# VSR_Mini_Mega_rev_1_300_new_XH_connector.net
KiCad netlist of a schematic drawn in EAGLE
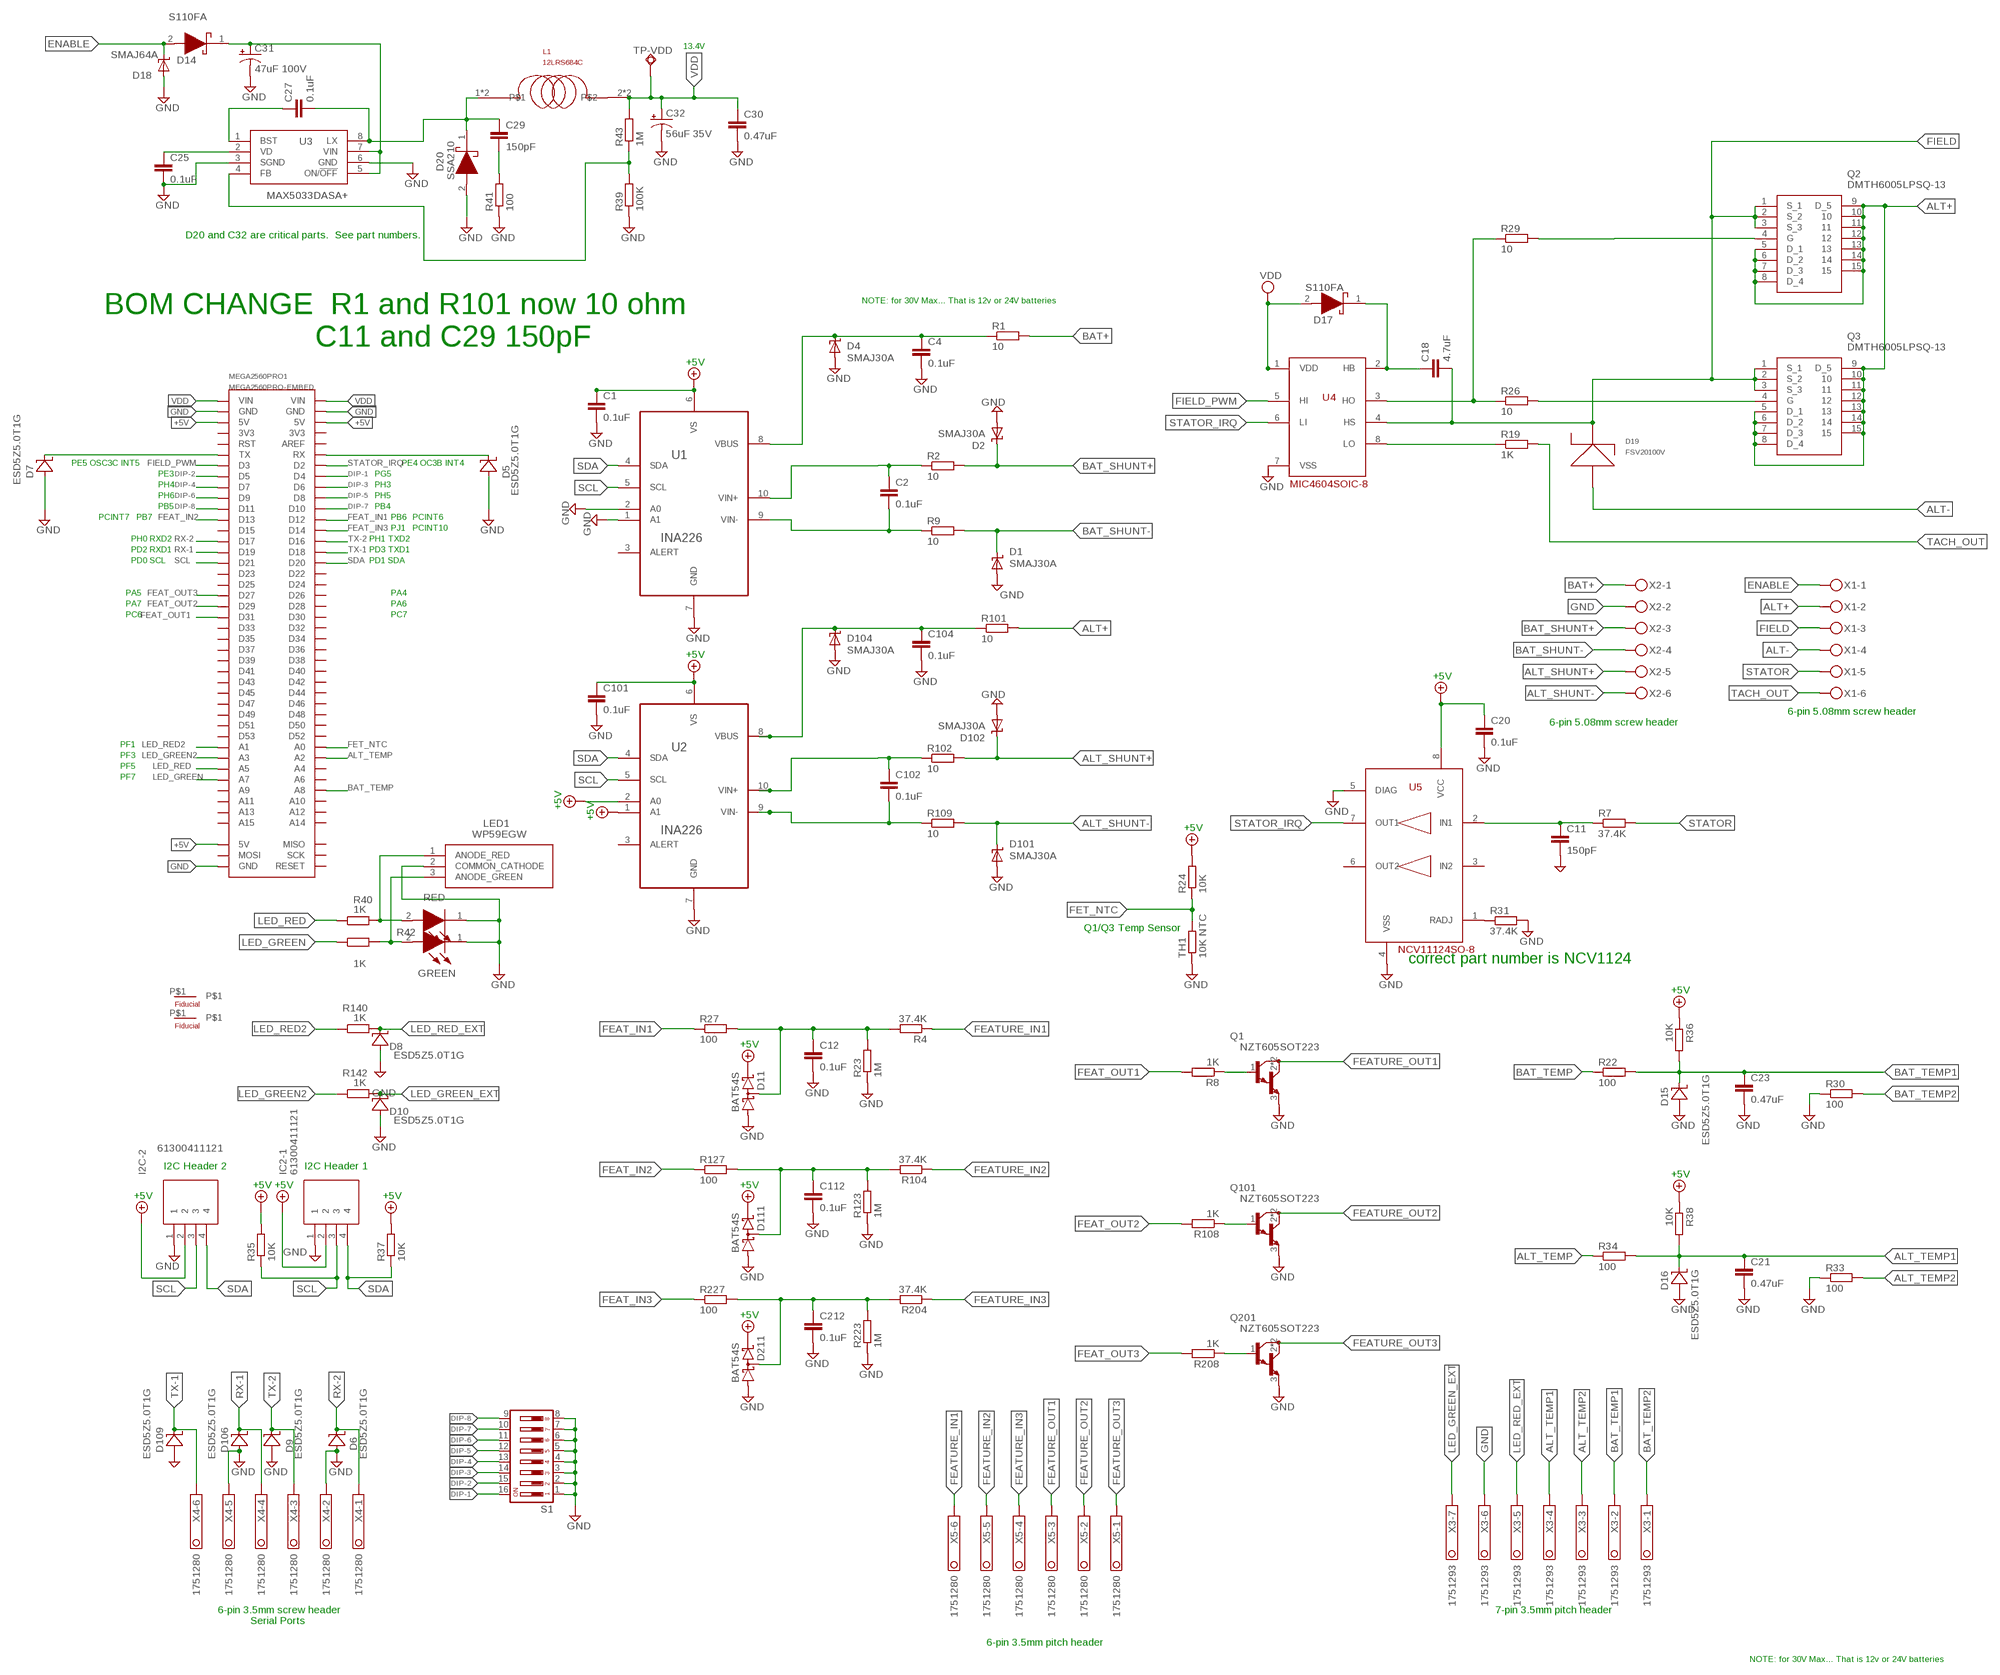
[diagram p0: schematic, sheet 1]

(export (version "E")
  (design (tool "Eeschema 10.0.6"))
  (components
    (comp (ref "C1")
      (value "0.1uF")
      (footprint "eagle-import:C0603")
      (libsource (lib "eagle-import") (part "C-EUC0603"))
    )
    (comp (ref "C2")
      (value "0.1uF")
      (footprint "eagle-import:C0603")
      (libsource (lib "eagle-import") (part "C-EUC0603"))
    )
    (comp (ref "C4")
      (value "0.1uF")
      (footprint "eagle-import:C0603")
      (libsource (lib "eagle-import") (part "C-EUC0603"))
    )
    (comp (ref "C11")
      (value "150pF")
      (footprint "eagle-import:C0603")
      (libsource (lib "eagle-import") (part "C-EUC0603"))
    )
    (comp (ref "C12")
      (value "0.1uF")
      (footprint "eagle-import:C0603")
      (libsource (lib "eagle-import") (part "C-EUC0603"))
    )
    (comp (ref "C18")
      (value "4.7uF")
      (footprint "eagle-import:C0603K")
      (libsource (lib "eagle-import") (part "C-EUC0603K"))
    )
    (comp (ref "C20")
      (value "0.1uF")
      (footprint "eagle-import:C0603")
      (libsource (lib "eagle-import") (part "C-EUC0603"))
    )
    (comp (ref "C21")
      (value "0.47uF")
      (footprint "eagle-import:C0603")
      (libsource (lib "eagle-import") (part "C-EUC0603"))
    )
    (comp (ref "C23")
      (value "0.47uF")
      (footprint "eagle-import:C0603")
      (libsource (lib "eagle-import") (part "C-EUC0603"))
    )
    (comp (ref "C25")
      (value "0.1uF")
      (footprint "eagle-import:C0603")
      (libsource (lib "eagle-import") (part "C-EUC0603"))
    )
    (comp (ref "C27")
      (value "0.1uF")
      (footprint "eagle-import:C0603")
      (libsource (lib "eagle-import") (part "C-EUC0603"))
    )
    (comp (ref "C29")
      (value "150pF")
      (footprint "eagle-import:C0603")
      (libsource (lib "eagle-import") (part "C-EUC0603"))
    )
    (comp (ref "C30")
      (value "0.47uF")
      (footprint "eagle-import:C0603")
      (libsource (lib "eagle-import") (part "C-EUC0603"))
    )
    (comp (ref "C31")
      (value "47uF 100V")
      (footprint "eagle-import:CAPPRD500W60D1000H1250B")
      (libsource (lib "eagle-import") (part "CPOL-USCAPPRD500W60D100H1250B"))
    )
    (comp (ref "C32")
      (value "56uF 35V")
      (footprint "eagle-import:CAPPRD250W50D630H1100B")
      (libsource (lib "eagle-import") (part "CPOL-US"))
    )
    (comp (ref "C101")
      (value "0.1uF")
      (footprint "eagle-import:C0603")
      (libsource (lib "eagle-import") (part "C-EUC0603"))
    )
    (comp (ref "C102")
      (value "0.1uF")
      (footprint "eagle-import:C0603")
      (libsource (lib "eagle-import") (part "C-EUC0603"))
    )
    (comp (ref "C104")
      (value "0.1uF")
      (footprint "eagle-import:C0603")
      (libsource (lib "eagle-import") (part "C-EUC0603"))
    )
    (comp (ref "C112")
      (value "0.1uF")
      (footprint "eagle-import:C0603")
      (libsource (lib "eagle-import") (part "C-EUC0603"))
    )
    (comp (ref "C212")
      (value "0.1uF")
      (footprint "eagle-import:C0603")
      (libsource (lib "eagle-import") (part "C-EUC0603"))
    )
    (comp (ref "D1")
      (value "SMAJ30A")
      (footprint "eagle-import:SMBJ")
      (libsource (lib "eagle-import") (part "SUPPRESSOR-SMBJ"))
    )
    (comp (ref "D2")
      (value "SMAJ30A")
      (footprint "eagle-import:SMBJ")
      (libsource (lib "eagle-import") (part "SUPPRESSOR-SMBJ"))
    )
    (comp (ref "D4")
      (value "SMAJ30A")
      (footprint "eagle-import:SMBJ")
      (libsource (lib "eagle-import") (part "SUPPRESSOR-SMBJ"))
    )
    (comp (ref "D5")
      (value "ESD5Z5.0T1G")
      (footprint "eagle-import:SOD523")
      (libsource (lib "eagle-import") (part "ESD5Z5.0T1G"))
    )
    (comp (ref "D6")
      (value "ESD5Z5.0T1G")
      (footprint "eagle-import:SOD523")
      (libsource (lib "eagle-import") (part "ESD5Z5.0T1G"))
    )
    (comp (ref "D7")
      (value "ESD5Z5.0T1G")
      (footprint "eagle-import:SOD523")
      (libsource (lib "eagle-import") (part "ESD5Z5.0T1G"))
    )
    (comp (ref "D8")
      (value "ESD5Z5.0T1G")
      (footprint "eagle-import:SOD523")
      (libsource (lib "eagle-import") (part "ESD5Z5.0T1G"))
    )
    (comp (ref "D9")
      (value "ESD5Z5.0T1G")
      (footprint "eagle-import:SOD523")
      (libsource (lib "eagle-import") (part "ESD5Z5.0T1G"))
    )
    (comp (ref "D10")
      (value "ESD5Z5.0T1G")
      (footprint "eagle-import:SOD523")
      (libsource (lib "eagle-import") (part "ESD5Z5.0T1G"))
    )
    (comp (ref "D11")
      (value "BAT54S")
      (footprint "eagle-import:SOT23")
      (libsource (lib "eagle-import") (part "BAT54S"))
    )
    (comp (ref "D14")
      (value "S110FA")
      (footprint "eagle-import:SODFL3618X143N")
      (fields (field (name "MOUSER_PART_NUMBER") "512-S110FA"))
      (libsource (lib "eagle-import") (part "S110FA"))
    )
    (comp (ref "D15")
      (value "ESD5Z5.0T1G")
      (footprint "eagle-import:SOD523")
      (libsource (lib "eagle-import") (part "ESD5Z5.0T1G"))
    )
    (comp (ref "D16")
      (value "ESD5Z5.0T1G")
      (footprint "eagle-import:SOD523")
      (libsource (lib "eagle-import") (part "ESD5Z5.0T1G"))
    )
    (comp (ref "D17")
      (value "S110FA")
      (footprint "eagle-import:SODFL3618X143N")
      (fields (field (name "MOUSER_PART_NUMBER") "512-S110FA"))
      (libsource (lib "eagle-import") (part "S110FA"))
    )
    (comp (ref "D18")
      (value "SMAJ64A")
      (footprint "eagle-import:SMBJ")
      (libsource (lib "eagle-import") (part "SUPPRESSOR-SMBJ"))
    )
    (comp (ref "D19")
      (value "FSV20100V")
      (footprint "eagle-import:TO-277")
      (fields (field (name "MF") "ON Semiconductor"))
      (libsource (lib "eagle-import") (part "FSV20100V"))
    )
    (comp (ref "D20")
      (value "SSA210")
      (footprint "eagle-import:DIOM5227X270N")
      (fields (field (name "MOUSER_PART_NUMBER") "512-SSA210"))
      (libsource (lib "eagle-import") (part "SSA210"))
    )
    (comp (ref "D101")
      (value "SMAJ30A")
      (footprint "eagle-import:SMBJ")
      (libsource (lib "eagle-import") (part "SUPPRESSOR-SMBJ"))
    )
    (comp (ref "D102")
      (value "SMAJ30A")
      (footprint "eagle-import:SMBJ")
      (libsource (lib "eagle-import") (part "SUPPRESSOR-SMBJ"))
    )
    (comp (ref "D104")
      (value "SMAJ30A")
      (footprint "eagle-import:SMBJ")
      (libsource (lib "eagle-import") (part "SUPPRESSOR-SMBJ"))
    )
    (comp (ref "D106")
      (value "ESD5Z5.0T1G")
      (footprint "eagle-import:SOD523")
      (libsource (lib "eagle-import") (part "ESD5Z5.0T1G"))
    )
    (comp (ref "D109")
      (value "ESD5Z5.0T1G")
      (footprint "eagle-import:SOD523")
      (libsource (lib "eagle-import") (part "ESD5Z5.0T1G"))
    )
    (comp (ref "D111")
      (value "BAT54S")
      (footprint "eagle-import:SOT23")
      (libsource (lib "eagle-import") (part "BAT54S"))
    )
    (comp (ref "D211")
      (value "BAT54S")
      (footprint "eagle-import:SOT23")
      (libsource (lib "eagle-import") (part "BAT54S"))
    )
    (comp (ref "FIDUCIAL1")
      (value "FIDUCIAL060")
      (footprint "eagle-import:FIDUCIAL060")
      (libsource (lib "eagle-import") (part "FIDUCIAL060"))
    )
    (comp (ref "FIDUCIAL2")
      (value "FIDUCIAL060")
      (footprint "eagle-import:FIDUCIAL060")
      (libsource (lib "eagle-import") (part "FIDUCIAL060"))
    )
    (comp (ref "GREEN")
      (value "599-0110-007F")
      (footprint "eagle-import:LEDM2012X90N")
      (fields (field (name "MOUSER_PART_NUMBER") "645-599-0110-007F"))
      (libsource (lib "eagle-import") (part "599-0110-007F"))
    )
    (comp (ref "I2C-2")
      (value "61300411121")
      (footprint "eagle-import:HDRV4W95P0X254_1X4_1016X254X85")
      (fields (field (name "MOUSER_PART_NUMBER") "710-61300411121"))
      (libsource (lib "eagle-import") (part "61300411121"))
    )
    (comp (ref "IC2-1")
      (value "61300411121")
      (footprint "eagle-import:HDRV4W95P0X254_1X4_1016X254X85")
      (fields (field (name "MOUSER_PART_NUMBER") "710-61300411121"))
      (libsource (lib "eagle-import") (part "61300411121"))
    )
    (comp (ref "L1")
      (value "12LRS684C")
      (footprint "eagle-import:IND_12LRS156C")
      (libsource (lib "eagle-import") (part "12LRS684C"))
    )
    (comp (ref "LED1")
      (value "WP59EGW")
      (footprint "eagle-import:T-1_3_4(5MM)_BI-COLOR_INDICATO")
      (fields (field (name "MOUSER_PART_NUMBER") "604-WP59EGW"))
      (libsource (lib "eagle-import") (part "WP59EGW"))
    )
    (comp (ref "MEGA2560PRO1")
      (value "MEGA2560PRO-EMBED")
      (footprint "eagle-import:MEGA2560PRO-EMBED")
      (libsource (lib "eagle-import") (part "MEGA2560PRO-EMBED"))
    )
    (comp (ref "Q1")
      (value "NZT605SOT223")
      (footprint "eagle-import:SOT223")
      (libsource (lib "eagle-import") (part "NZT605SOT223"))
    )
    (comp (ref "Q2")
      (value "DMTH6005LPSQ-13")
      (footprint "eagle-import:DMTH6005LPSQ13")
      (fields (field (name "MOUSER_PART_NUMBER") "621-DMTH6005LPSQ-13"))
      (libsource (lib "eagle-import") (part "DMTH6005LPSQ-13"))
    )
    (comp (ref "Q3")
      (value "DMTH6005LPSQ-13")
      (footprint "eagle-import:DMTH6005LPSQ13")
      (fields (field (name "MOUSER_PART_NUMBER") "621-DMTH6005LPSQ-13"))
      (libsource (lib "eagle-import") (part "DMTH6005LPSQ-13"))
    )
    (comp (ref "Q101")
      (value "NZT605SOT223")
      (footprint "eagle-import:SOT223")
      (libsource (lib "eagle-import") (part "NZT605SOT223"))
    )
    (comp (ref "Q201")
      (value "NZT605SOT223")
      (footprint "eagle-import:SOT223")
      (libsource (lib "eagle-import") (part "NZT605SOT223"))
    )
    (comp (ref "R1")
      (value "10")
      (footprint "eagle-import:R0603")
      (libsource (lib "eagle-import") (part "R-EU_R0603"))
    )
    (comp (ref "R2")
      (value "10")
      (footprint "eagle-import:R0603")
      (libsource (lib "eagle-import") (part "R-EU_R0603"))
    )
    (comp (ref "R4")
      (value "37.4K")
      (footprint "eagle-import:R0603")
      (libsource (lib "eagle-import") (part "R-EU_R0603"))
    )
    (comp (ref "R7")
      (value "37.4K")
      (footprint "eagle-import:R0603")
      (libsource (lib "eagle-import") (part "R-EU_R0603"))
    )
    (comp (ref "R8")
      (value "1K")
      (footprint "eagle-import:R0603")
      (libsource (lib "eagle-import") (part "R-EU_R0603"))
    )
    (comp (ref "R9")
      (value "10")
      (footprint "eagle-import:R0603")
      (libsource (lib "eagle-import") (part "R-EU_R0603"))
    )
    (comp (ref "R19")
      (value "1K")
      (footprint "eagle-import:R0603")
      (libsource (lib "eagle-import") (part "R-EU_R0603"))
    )
    (comp (ref "R22")
      (value "100")
      (footprint "eagle-import:R0603")
      (libsource (lib "eagle-import") (part "R-EU_R0603"))
    )
    (comp (ref "R23")
      (value "1M")
      (footprint "eagle-import:R0603")
      (libsource (lib "eagle-import") (part "R-EU_R0603"))
    )
    (comp (ref "R24")
      (value "10K")
      (footprint "eagle-import:R0603")
      (libsource (lib "eagle-import") (part "R-EU_R0603"))
    )
    (comp (ref "R26")
      (value "10")
      (footprint "eagle-import:R0603")
      (libsource (lib "eagle-import") (part "R-EU_R0603"))
    )
    (comp (ref "R27")
      (value "100")
      (footprint "eagle-import:R0603")
      (libsource (lib "eagle-import") (part "R-EU_R0603"))
    )
    (comp (ref "R29")
      (value "10")
      (footprint "eagle-import:R0603")
      (libsource (lib "eagle-import") (part "R-EU_R0603"))
    )
    (comp (ref "R30")
      (value "100")
      (footprint "eagle-import:R0603")
      (libsource (lib "eagle-import") (part "R-EU_R0603"))
    )
    (comp (ref "R31")
      (value "37.4K")
      (footprint "eagle-import:R0603")
      (libsource (lib "eagle-import") (part "R-EU_R0603"))
    )
    (comp (ref "R33")
      (value "100")
      (footprint "eagle-import:R0603")
      (libsource (lib "eagle-import") (part "R-EU_R0603"))
    )
    (comp (ref "R34")
      (value "100")
      (footprint "eagle-import:R0603")
      (libsource (lib "eagle-import") (part "R-EU_R0603"))
    )
    (comp (ref "R35")
      (value "10K")
      (footprint "eagle-import:R0603")
      (libsource (lib "eagle-import") (part "R-EU_R0603"))
    )
    (comp (ref "R36")
      (value "10K")
      (footprint "eagle-import:R0603")
      (libsource (lib "eagle-import") (part "R-EU_R0603"))
    )
    (comp (ref "R37")
      (value "10K")
      (footprint "eagle-import:R0603")
      (libsource (lib "eagle-import") (part "R-EU_R0603"))
    )
    (comp (ref "R38")
      (value "10K")
      (footprint "eagle-import:R0603")
      (libsource (lib "eagle-import") (part "R-EU_R0603"))
    )
    (comp (ref "R39")
      (value "100K")
      (footprint "eagle-import:R0603")
      (libsource (lib "eagle-import") (part "R-EU_R0603"))
    )
    (comp (ref "R40")
      (value "1K")
      (footprint "eagle-import:R0603")
      (libsource (lib "eagle-import") (part "R-EU_R0603"))
    )
    (comp (ref "R41")
      (value "100")
      (footprint "eagle-import:R0603")
      (libsource (lib "eagle-import") (part "R-EU_R0603"))
    )
    (comp (ref "R42")
      (value "1K")
      (footprint "eagle-import:R0603")
      (libsource (lib "eagle-import") (part "R-EU_R0603"))
    )
    (comp (ref "R43")
      (value "1M")
      (footprint "eagle-import:R0603")
      (libsource (lib "eagle-import") (part "R-EU_R0603"))
    )
    (comp (ref "R101")
      (value "10")
      (footprint "eagle-import:R0603")
      (libsource (lib "eagle-import") (part "R-EU_R0603"))
    )
    (comp (ref "R102")
      (value "10")
      (footprint "eagle-import:R0603")
      (libsource (lib "eagle-import") (part "R-EU_R0603"))
    )
    (comp (ref "R104")
      (value "37.4K")
      (footprint "eagle-import:R0603")
      (libsource (lib "eagle-import") (part "R-EU_R0603"))
    )
    (comp (ref "R108")
      (value "1K")
      (footprint "eagle-import:R0603")
      (libsource (lib "eagle-import") (part "R-EU_R0603"))
    )
    (comp (ref "R109")
      (value "10")
      (footprint "eagle-import:R0603")
      (libsource (lib "eagle-import") (part "R-EU_R0603"))
    )
    (comp (ref "R123")
      (value "1M")
      (footprint "eagle-import:R0603")
      (libsource (lib "eagle-import") (part "R-EU_R0603"))
    )
    (comp (ref "R127")
      (value "100")
      (footprint "eagle-import:R0603")
      (libsource (lib "eagle-import") (part "R-EU_R0603"))
    )
    (comp (ref "R140")
      (value "1K")
      (footprint "eagle-import:R0603")
      (libsource (lib "eagle-import") (part "R-EU_R0603"))
    )
    (comp (ref "R142")
      (value "1K")
      (footprint "eagle-import:R0603")
      (libsource (lib "eagle-import") (part "R-EU_R0603"))
    )
    (comp (ref "R204")
      (value "37.4K")
      (footprint "eagle-import:R0603")
      (libsource (lib "eagle-import") (part "R-EU_R0603"))
    )
    (comp (ref "R208")
      (value "1K")
      (footprint "eagle-import:R0603")
      (libsource (lib "eagle-import") (part "R-EU_R0603"))
    )
    (comp (ref "R223")
      (value "1M")
      (footprint "eagle-import:R0603")
      (libsource (lib "eagle-import") (part "R-EU_R0603"))
    )
    (comp (ref "R227")
      (value "100")
      (footprint "eagle-import:R0603")
      (libsource (lib "eagle-import") (part "R-EU_R0603"))
    )
    (comp (ref "RED")
      (value "599-0110-007F")
      (footprint "eagle-import:LEDM2012X90N")
      (fields (field (name "MOUSER_PART_NUMBER") "645-599-0110-007F"))
      (libsource (lib "eagle-import") (part "599-0110-007F"))
    )
    (comp (ref "S1")
      (value "DP08")
      (footprint "eagle-import:DP-08")
      (libsource (lib "eagle-import") (part "DP08"))
    )
    (comp (ref "TH1")
      (value "10K NTC")
      (footprint "eagle-import:R0402")
      (libsource (lib "eagle-import") (part "R-EU_R0402"))
    )
    (comp (ref "TP-VDD")
      (value "TPSQTP20SQ")
      (footprint "eagle-import:TP20SQ")
      (libsource (lib "eagle-import") (part "TPSQTP20SQ"))
    )
    (comp (ref "U1")
      (value "INA226")
      (footprint "eagle-import:SOP50P490X110-10N")
      (fields (field (name "MPN") "INA226AIDGSR"))
      (libsource (lib "eagle-import") (part "INA226"))
    )
    (comp (ref "U2")
      (value "INA226")
      (footprint "eagle-import:SOP50P490X110-10N")
      (fields (field (name "MPN") "INA226AIDGSR"))
      (libsource (lib "eagle-import") (part "INA226"))
    )
    (comp (ref "U3")
      (value "MAX5033DASA+")
      (footprint "eagle-import:SOIC127P600X175-8N")
      (fields (field (name "MOUSER_PART_NUMBER") "700-MAX5033DASA"))
      (libsource (lib "eagle-import") (part "MAX5033DASA+"))
    )
    (comp (ref "U4")
      (value "MIC4604SOIC-8")
      (footprint "eagle-import:SOIC8")
      (libsource (lib "eagle-import") (part "MIC4604SOIC-8"))
    )
    (comp (ref "U5")
      (value "NCV11124SO-8")
      (footprint "eagle-import:SO-8")
      (libsource (lib "eagle-import") (part "NCV11124SO-8"))
    )
    (comp (ref "X1")
      (value "MKDSN1,5/6-5,08")
      (footprint "eagle-import:MKDSN1,5_6-5,08")
      (libsource (lib "eagle-import") (part "MKDSN1,5/6-5,08"))
    )
    (comp (ref "X2")
      (value "MKDSN1,5/6-5,08")
      (footprint "eagle-import:MKDSN1,5_6-5,08")
      (libsource (lib "eagle-import") (part "MKDSN1,5/6-5,08"))
    )
    (comp (ref "X3")
      (value "1751293")
      (footprint "eagle-import:1751293")
      (libsource (lib "eagle-import") (part "1751293"))
    )
    (comp (ref "X4")
      (value "1751280")
      (footprint "eagle-import:1751280")
      (libsource (lib "eagle-import") (part "1751280"))
    )
    (comp (ref "X5")
      (value "1751280")
      (footprint "eagle-import:1751280")
      (libsource (lib "eagle-import") (part "1751280"))
    )
  )
  (nets
    (net (code "1") (name "+5V") (class "Default")
      (node (ref "C1") (pin "1") (pinfunction "1_1") (pintype "passive"))
      (node (ref "C101") (pin "1") (pinfunction "1_1") (pintype "passive"))
      (node (ref "C20") (pin "1") (pinfunction "1_1") (pintype "passive"))
      (node (ref "D11") (pin "2") (pinfunction "C2_2") (pintype "passive"))
      (node (ref "D111") (pin "2") (pinfunction "C2_2") (pintype "passive"))
      (node (ref "D211") (pin "2") (pinfunction "C2_2") (pintype "passive"))
      (node (ref "I2C-2") (pin "2") (pinfunction "2_2") (pintype "bidirectional"))
      (node (ref "IC2-1") (pin "2") (pinfunction "2_2") (pintype "bidirectional"))
      (node (ref "MEGA2560PRO1") (pin "5V@1") (pinfunction "5V_5V@1") (pintype "bidirectional"))
      (node (ref "MEGA2560PRO1") (pin "5V@2") (pinfunction "5V_5V@2") (pintype "bidirectional"))
      (node (ref "MEGA2560PRO1") (pin "5V@3") (pinfunction "5V_5V@3") (pintype "bidirectional"))
      (node (ref "R24") (pin "2") (pinfunction "2_2") (pintype "passive"))
      (node (ref "R35") (pin "2") (pinfunction "2_2") (pintype "passive"))
      (node (ref "R36") (pin "1") (pinfunction "1_1") (pintype "passive"))
      (node (ref "R37") (pin "2") (pinfunction "2_2") (pintype "passive"))
      (node (ref "R38") (pin "1") (pinfunction "1_1") (pintype "passive"))
      (node (ref "U1") (pin "6") (pinfunction "VS_6") (pintype "power_in"))
      (node (ref "U2") (pin "1") (pinfunction "A1_1") (pintype "input"))
      (node (ref "U2") (pin "2") (pinfunction "A0_2") (pintype "input"))
      (node (ref "U2") (pin "6") (pinfunction "VS_6") (pintype "power_in"))
      (node (ref "U5") (pin "8") (pinfunction "VCC_8") (pintype "bidirectional"))
    )
    (net (code "2") (name "ALT+") (class "Default")
      (node (ref "Q2") (pin "10") (pinfunction "10_10") (pintype "bidirectional"))
      (node (ref "Q2") (pin "11") (pinfunction "11_11") (pintype "bidirectional"))
      (node (ref "Q2") (pin "12") (pinfunction "12_12") (pintype "bidirectional"))
      (node (ref "Q2") (pin "13") (pinfunction "13_13") (pintype "bidirectional"))
      (node (ref "Q2") (pin "14") (pinfunction "14_14") (pintype "bidirectional"))
      (node (ref "Q2") (pin "15") (pinfunction "15_15") (pintype "bidirectional"))
      (node (ref "Q2") (pin "5") (pinfunction "D_1_5") (pintype "bidirectional"))
      (node (ref "Q2") (pin "6") (pinfunction "D_2_6") (pintype "bidirectional"))
      (node (ref "Q2") (pin "7") (pinfunction "D_3_7") (pintype "bidirectional"))
      (node (ref "Q2") (pin "8") (pinfunction "D_4_8") (pintype "bidirectional"))
      (node (ref "Q2") (pin "9") (pinfunction "D_5_9") (pintype "bidirectional"))
      (node (ref "Q3") (pin "10") (pinfunction "10_10") (pintype "bidirectional"))
      (node (ref "Q3") (pin "11") (pinfunction "11_11") (pintype "bidirectional"))
      (node (ref "Q3") (pin "12") (pinfunction "12_12") (pintype "bidirectional"))
      (node (ref "Q3") (pin "13") (pinfunction "13_13") (pintype "bidirectional"))
      (node (ref "Q3") (pin "14") (pinfunction "14_14") (pintype "bidirectional"))
      (node (ref "Q3") (pin "15") (pinfunction "15_15") (pintype "bidirectional"))
      (node (ref "Q3") (pin "5") (pinfunction "D_1_5") (pintype "bidirectional"))
      (node (ref "Q3") (pin "6") (pinfunction "D_2_6") (pintype "bidirectional"))
      (node (ref "Q3") (pin "7") (pinfunction "D_3_7") (pintype "bidirectional"))
      (node (ref "Q3") (pin "8") (pinfunction "D_4_8") (pintype "bidirectional"))
      (node (ref "Q3") (pin "9") (pinfunction "D_5_9") (pintype "bidirectional"))
      (node (ref "R101") (pin "2") (pinfunction "2_2") (pintype "passive"))
      (node (ref "X1") (pin "2") (pinfunction "KL_2") (pintype "passive"))
    )
    (net (code "3") (name "ALT-") (class "Default")
      (node (ref "D19") (pin "1") (pinfunction "P$2_1") (pintype "bidirectional"))
      (node (ref "D19") (pin "2") (pinfunction "P$2_2") (pintype "bidirectional"))
      (node (ref "X1") (pin "4") (pinfunction "KL_4") (pintype "passive"))
    )
    (net (code "4") (name "ALT_SHUNT+") (class "Default")
      (node (ref "D102") (pin "C") (pinfunction "C_C") (pintype "passive"))
      (node (ref "R102") (pin "2") (pinfunction "2_2") (pintype "passive"))
      (node (ref "X2") (pin "5") (pinfunction "KL_5") (pintype "passive"))
    )
    (net (code "5") (name "ALT_SHUNT-") (class "Default")
      (node (ref "D101") (pin "C") (pinfunction "C_C") (pintype "passive"))
      (node (ref "R109") (pin "2") (pinfunction "2_2") (pintype "passive"))
      (node (ref "X2") (pin "6") (pinfunction "KL_6") (pintype "passive"))
    )
    (net (code "6") (name "ALT_TEMP") (class "Default")
      (node (ref "MEGA2560PRO1") (pin "A2") (pinfunction "A2_A2") (pintype "bidirectional"))
      (node (ref "R34") (pin "1") (pinfunction "1_1") (pintype "passive"))
    )
    (net (code "7") (name "ALT_TEMP1") (class "Default")
      (node (ref "C21") (pin "1") (pinfunction "1_1") (pintype "passive"))
      (node (ref "D16") (pin "C") (pinfunction "C_C") (pintype "passive"))
      (node (ref "R34") (pin "2") (pinfunction "2_2") (pintype "passive"))
      (node (ref "R38") (pin "2") (pinfunction "2_2") (pintype "passive"))
      (node (ref "X3") (pin "4") (pinfunction "K_4") (pintype "passive"))
    )
    (net (code "8") (name "ALT_TEMP2") (class "Default")
      (node (ref "R33") (pin "2") (pinfunction "2_2") (pintype "passive"))
      (node (ref "X3") (pin "3") (pinfunction "K_3") (pintype "passive"))
    )
    (net (code "9") (name "BAT+") (class "Default")
      (node (ref "R1") (pin "2") (pinfunction "2_2") (pintype "passive"))
      (node (ref "X2") (pin "1") (pinfunction "KL_1") (pintype "passive"))
    )
    (net (code "10") (name "BAT_SHUNT+") (class "Default")
      (node (ref "D2") (pin "C") (pinfunction "C_C") (pintype "passive"))
      (node (ref "R2") (pin "2") (pinfunction "2_2") (pintype "passive"))
      (node (ref "X2") (pin "3") (pinfunction "KL_3") (pintype "passive"))
    )
    (net (code "11") (name "BAT_SHUNT-") (class "Default")
      (node (ref "D1") (pin "C") (pinfunction "C_C") (pintype "passive"))
      (node (ref "R9") (pin "2") (pinfunction "2_2") (pintype "passive"))
      (node (ref "X2") (pin "4") (pinfunction "KL_4") (pintype "passive"))
    )
    (net (code "12") (name "BAT_TEMP") (class "Default")
      (node (ref "MEGA2560PRO1") (pin "A8") (pinfunction "A8_A8") (pintype "bidirectional"))
      (node (ref "R22") (pin "1") (pinfunction "1_1") (pintype "passive"))
    )
    (net (code "13") (name "BAT_TEMP1") (class "Default")
      (node (ref "C23") (pin "1") (pinfunction "1_1") (pintype "passive"))
      (node (ref "D15") (pin "C") (pinfunction "C_C") (pintype "passive"))
      (node (ref "R22") (pin "2") (pinfunction "2_2") (pintype "passive"))
      (node (ref "R36") (pin "2") (pinfunction "2_2") (pintype "passive"))
      (node (ref "X3") (pin "2") (pinfunction "K_2") (pintype "passive"))
    )
    (net (code "14") (name "BAT_TEMP2") (class "Default")
      (node (ref "R30") (pin "2") (pinfunction "2_2") (pintype "passive"))
      (node (ref "X3") (pin "1") (pinfunction "K_1") (pintype "passive"))
    )
    (net (code "15") (name "DIP-1") (class "Default")
      (node (ref "MEGA2560PRO1") (pin "D4") (pinfunction "D4_D4") (pintype "bidirectional"))
      (node (ref "S1") (pin "16") (pinfunction "16_16") (pintype "passive"))
    )
    (net (code "16") (name "DIP-2") (class "Default")
      (node (ref "MEGA2560PRO1") (pin "D5") (pinfunction "D5_D5") (pintype "bidirectional"))
      (node (ref "S1") (pin "15") (pinfunction "15_15") (pintype "passive"))
    )
    (net (code "17") (name "DIP-3") (class "Default")
      (node (ref "MEGA2560PRO1") (pin "D6") (pinfunction "D6_D6") (pintype "bidirectional"))
      (node (ref "S1") (pin "14") (pinfunction "14_14") (pintype "passive"))
    )
    (net (code "18") (name "DIP-4") (class "Default")
      (node (ref "MEGA2560PRO1") (pin "D7") (pinfunction "D7_D7") (pintype "bidirectional"))
      (node (ref "S1") (pin "13") (pinfunction "13_13") (pintype "passive"))
    )
    (net (code "19") (name "DIP-5") (class "Default")
      (node (ref "MEGA2560PRO1") (pin "D8") (pinfunction "D8_D8") (pintype "bidirectional"))
      (node (ref "S1") (pin "12") (pinfunction "12_12") (pintype "passive"))
    )
    (net (code "20") (name "DIP-6") (class "Default")
      (node (ref "MEGA2560PRO1") (pin "D9") (pinfunction "D9_D9") (pintype "bidirectional"))
      (node (ref "S1") (pin "11") (pinfunction "11_11") (pintype "passive"))
    )
    (net (code "21") (name "DIP-7") (class "Default")
      (node (ref "MEGA2560PRO1") (pin "D10") (pinfunction "D10_D10") (pintype "bidirectional"))
      (node (ref "S1") (pin "10") (pinfunction "10_10") (pintype "passive"))
    )
    (net (code "22") (name "DIP-8") (class "Default")
      (node (ref "MEGA2560PRO1") (pin "D11") (pinfunction "D11_D11") (pintype "bidirectional"))
      (node (ref "S1") (pin "9") (pinfunction "9_9") (pintype "passive"))
    )
    (net (code "23") (name "ENABLE") (class "Default")
      (node (ref "D14") (pin "2") (pinfunction "A_2") (pintype "bidirectional"))
      (node (ref "D18") (pin "C") (pinfunction "C_C") (pintype "passive"))
      (node (ref "X1") (pin "1") (pinfunction "KL_1") (pintype "passive"))
    )
    (net (code "24") (name "FEATURE_IN1") (class "Default")
      (node (ref "R4") (pin "1") (pinfunction "1_1") (pintype "passive"))
      (node (ref "X5") (pin "6") (pinfunction "K_6") (pintype "passive"))
    )
    (net (code "25") (name "FEATURE_IN2") (class "Default")
      (node (ref "R104") (pin "1") (pinfunction "1_1") (pintype "passive"))
      (node (ref "X5") (pin "5") (pinfunction "K_5") (pintype "passive"))
    )
    (net (code "26") (name "FEATURE_IN3") (class "Default")
      (node (ref "R204") (pin "1") (pinfunction "1_1") (pintype "passive"))
      (node (ref "X5") (pin "4") (pinfunction "K_4") (pintype "passive"))
    )
    (net (code "27") (name "FEATURE_OUT1") (class "Default")
      (node (ref "Q1") (pin "2") (pinfunction "C_2") (pintype "passive"))
      (node (ref "Q1") (pin "4") (pinfunction "C_4") (pintype "passive"))
      (node (ref "X5") (pin "3") (pinfunction "K_3") (pintype "passive"))
    )
    (net (code "28") (name "FEATURE_OUT2") (class "Default")
      (node (ref "Q101") (pin "2") (pinfunction "C_2") (pintype "passive"))
      (node (ref "Q101") (pin "4") (pinfunction "C_4") (pintype "passive"))
      (node (ref "X5") (pin "2") (pinfunction "K_2") (pintype "passive"))
    )
    (net (code "29") (name "FEATURE_OUT3") (class "Default")
      (node (ref "Q201") (pin "2") (pinfunction "C_2") (pintype "passive"))
      (node (ref "Q201") (pin "4") (pinfunction "C_4") (pintype "passive"))
      (node (ref "X5") (pin "1") (pinfunction "K_1") (pintype "passive"))
    )
    (net (code "30") (name "FEAT_IN1") (class "Default")
      (node (ref "MEGA2560PRO1") (pin "D12") (pinfunction "D12_D12") (pintype "bidirectional"))
      (node (ref "R27") (pin "1") (pinfunction "1_1") (pintype "passive"))
    )
    (net (code "31") (name "FEAT_IN2") (class "Default")
      (node (ref "MEGA2560PRO1") (pin "D13") (pinfunction "D13_D13") (pintype "bidirectional"))
      (node (ref "R127") (pin "1") (pinfunction "1_1") (pintype "passive"))
    )
    (net (code "32") (name "FEAT_IN3") (class "Default")
      (node (ref "MEGA2560PRO1") (pin "D14") (pinfunction "D14_D14") (pintype "bidirectional"))
      (node (ref "R227") (pin "1") (pinfunction "1_1") (pintype "passive"))
    )
    (net (code "33") (name "FEAT_OUT1") (class "Default")
      (node (ref "MEGA2560PRO1") (pin "D31") (pinfunction "D31_D31") (pintype "bidirectional"))
      (node (ref "R8") (pin "2") (pinfunction "2_2") (pintype "passive"))
    )
    (net (code "34") (name "FEAT_OUT2") (class "Default")
      (node (ref "MEGA2560PRO1") (pin "D29") (pinfunction "D29_D29") (pintype "bidirectional"))
      (node (ref "R108") (pin "2") (pinfunction "2_2") (pintype "passive"))
    )
    (net (code "35") (name "FEAT_OUT3") (class "Default")
      (node (ref "MEGA2560PRO1") (pin "D27") (pinfunction "D27_D27") (pintype "bidirectional"))
      (node (ref "R208") (pin "2") (pinfunction "2_2") (pintype "passive"))
    )
    (net (code "36") (name "FET_NTC") (class "Default")
      (node (ref "MEGA2560PRO1") (pin "A0") (pinfunction "A0_A0") (pintype "bidirectional"))
      (node (ref "R24") (pin "1") (pinfunction "1_1") (pintype "passive"))
      (node (ref "TH1") (pin "2") (pinfunction "2_2") (pintype "passive"))
    )
    (net (code "37") (name "FIELD") (class "Default")
      (node (ref "C18") (pin "2") (pinfunction "2_2") (pintype "passive"))
      (node (ref "D19") (pin "3") (pinfunction "P$1_3") (pintype "bidirectional"))
      (node (ref "Q2") (pin "1") (pinfunction "S_1_1") (pintype "bidirectional"))
      (node (ref "Q2") (pin "2") (pinfunction "S_2_2") (pintype "bidirectional"))
      (node (ref "Q2") (pin "3") (pinfunction "S_3_3") (pintype "bidirectional"))
      (node (ref "Q3") (pin "1") (pinfunction "S_1_1") (pintype "bidirectional"))
      (node (ref "Q3") (pin "2") (pinfunction "S_2_2") (pintype "bidirectional"))
      (node (ref "Q3") (pin "3") (pinfunction "S_3_3") (pintype "bidirectional"))
      (node (ref "U4") (pin "4") (pinfunction "HS_4") (pintype "bidirectional"))
      (node (ref "X1") (pin "3") (pinfunction "KL_3") (pintype "passive"))
    )
    (net (code "38") (name "FIELD_PWM") (class "Default")
      (node (ref "MEGA2560PRO1") (pin "D3") (pinfunction "D3_D3") (pintype "bidirectional"))
      (node (ref "U4") (pin "5") (pinfunction "HI_5") (pintype "bidirectional"))
    )
    (net (code "39") (name "GND") (class "Default")
      (node (ref "C1") (pin "2") (pinfunction "2_2") (pintype "passive"))
      (node (ref "C101") (pin "2") (pinfunction "2_2") (pintype "passive"))
      (node (ref "C104") (pin "2") (pinfunction "2_2") (pintype "passive"))
      (node (ref "C11") (pin "2") (pinfunction "2_2") (pintype "passive"))
      (node (ref "C112") (pin "2") (pinfunction "2_2") (pintype "passive"))
      (node (ref "C12") (pin "2") (pinfunction "2_2") (pintype "passive"))
      (node (ref "C20") (pin "2") (pinfunction "2_2") (pintype "passive"))
      (node (ref "C21") (pin "2") (pinfunction "2_2") (pintype "passive"))
      (node (ref "C212") (pin "2") (pinfunction "2_2") (pintype "passive"))
      (node (ref "C23") (pin "2") (pinfunction "2_2") (pintype "passive"))
      (node (ref "C25") (pin "2") (pinfunction "2_2") (pintype "passive"))
      (node (ref "C30") (pin "2") (pinfunction "2_2") (pintype "passive"))
      (node (ref "C31") (pin "2") (pinfunction "-_2") (pintype "passive"))
      (node (ref "C32") (pin "2") (pinfunction "-_2") (pintype "passive"))
      (node (ref "C4") (pin "2") (pinfunction "2_2") (pintype "passive"))
      (node (ref "D1") (pin "A") (pinfunction "A_A") (pintype "passive"))
      (node (ref "D10") (pin "A") (pinfunction "A_A") (pintype "passive"))
      (node (ref "D101") (pin "A") (pinfunction "A_A") (pintype "passive"))
      (node (ref "D102") (pin "A") (pinfunction "A_A") (pintype "passive"))
      (node (ref "D104") (pin "A") (pinfunction "A_A") (pintype "passive"))
      (node (ref "D106") (pin "A") (pinfunction "A_A") (pintype "passive"))
      (node (ref "D109") (pin "A") (pinfunction "A_A") (pintype "passive"))
      (node (ref "D11") (pin "1") (pinfunction "A1_1") (pintype "passive"))
      (node (ref "D111") (pin "1") (pinfunction "A1_1") (pintype "passive"))
      (node (ref "D15") (pin "A") (pinfunction "A_A") (pintype "passive"))
      (node (ref "D16") (pin "A") (pinfunction "A_A") (pintype "passive"))
      (node (ref "D18") (pin "A") (pinfunction "A_A") (pintype "passive"))
      (node (ref "D2") (pin "A") (pinfunction "A_A") (pintype "passive"))
      (node (ref "D20") (pin "2") (pinfunction "A_2") (pintype "bidirectional"))
      (node (ref "D211") (pin "1") (pinfunction "A1_1") (pintype "passive"))
      (node (ref "D4") (pin "A") (pinfunction "A_A") (pintype "passive"))
      (node (ref "D5") (pin "A") (pinfunction "A_A") (pintype "passive"))
      (node (ref "D6") (pin "A") (pinfunction "A_A") (pintype "passive"))
      (node (ref "D7") (pin "A") (pinfunction "A_A") (pintype "passive"))
      (node (ref "D8") (pin "A") (pinfunction "A_A") (pintype "passive"))
      (node (ref "D9") (pin "A") (pinfunction "A_A") (pintype "passive"))
      (node (ref "GREEN") (pin "1") (pinfunction "K_1") (pintype "bidirectional"))
      (node (ref "I2C-2") (pin "1") (pinfunction "1_1") (pintype "bidirectional"))
      (node (ref "IC2-1") (pin "1") (pinfunction "1_1") (pintype "bidirectional"))
      (node (ref "LED1") (pin "2") (pinfunction "COMMON_CATHODE_2") (pintype "bidirectional"))
      (node (ref "MEGA2560PRO1") (pin "GND@1") (pinfunction "GND_GND@1") (pintype "bidirectional"))
      (node (ref "MEGA2560PRO1") (pin "GND@2") (pinfunction "GND_GND@2") (pintype "bidirectional"))
      (node (ref "MEGA2560PRO1") (pin "GND@3") (pinfunction "GND_GND@3") (pintype "bidirectional"))
      (node (ref "Q1") (pin "3") (pinfunction "E_3") (pintype "passive"))
      (node (ref "Q101") (pin "3") (pinfunction "E_3") (pintype "passive"))
      (node (ref "Q201") (pin "3") (pinfunction "E_3") (pintype "passive"))
      (node (ref "R123") (pin "1") (pinfunction "1_1") (pintype "passive"))
      (node (ref "R223") (pin "1") (pinfunction "1_1") (pintype "passive"))
      (node (ref "R23") (pin "1") (pinfunction "1_1") (pintype "passive"))
      (node (ref "R30") (pin "1") (pinfunction "1_1") (pintype "passive"))
      (node (ref "R31") (pin "2") (pinfunction "2_2") (pintype "passive"))
      (node (ref "R33") (pin "1") (pinfunction "1_1") (pintype "passive"))
      (node (ref "R39") (pin "1") (pinfunction "1_1") (pintype "passive"))
      (node (ref "R41") (pin "1") (pinfunction "1_1") (pintype "passive"))
      (node (ref "RED") (pin "1") (pinfunction "K_1") (pintype "bidirectional"))
      (node (ref "S1") (pin "1") (pinfunction "1_1") (pintype "passive"))
      (node (ref "S1") (pin "2") (pinfunction "2_2") (pintype "passive"))
      (node (ref "S1") (pin "3") (pinfunction "3_3") (pintype "passive"))
      (node (ref "S1") (pin "4") (pinfunction "4_4") (pintype "passive"))
      (node (ref "S1") (pin "5") (pinfunction "5_5") (pintype "passive"))
      (node (ref "S1") (pin "6") (pinfunction "6_6") (pintype "passive"))
      (node (ref "S1") (pin "7") (pinfunction "7_7") (pintype "passive"))
      (node (ref "S1") (pin "8") (pinfunction "8_8") (pintype "passive"))
      (node (ref "TH1") (pin "1") (pinfunction "1_1") (pintype "passive"))
      (node (ref "U1") (pin "1") (pinfunction "A1_1") (pintype "input"))
      (node (ref "U1") (pin "2") (pinfunction "A0_2") (pintype "input"))
      (node (ref "U1") (pin "7") (pinfunction "GND_7") (pintype "passive"))
      (node (ref "U2") (pin "7") (pinfunction "GND_7") (pintype "passive"))
      (node (ref "U3") (pin "3") (pinfunction "SGND_3") (pintype "bidirectional"))
      (node (ref "U3") (pin "6") (pinfunction "GND_6") (pintype "bidirectional"))
      (node (ref "U4") (pin "7") (pinfunction "VSS_7") (pintype "bidirectional"))
      (node (ref "U5") (pin "4") (pinfunction "VSS_4") (pintype "bidirectional"))
      (node (ref "U5") (pin "5") (pinfunction "DIAG_5") (pintype "bidirectional"))
      (node (ref "X2") (pin "2") (pinfunction "KL_2") (pintype "passive"))
      (node (ref "X3") (pin "6") (pinfunction "K_6") (pintype "passive"))
      (node (ref "X4") (pin "2") (pinfunction "K_2") (pintype "passive"))
      (node (ref "X4") (pin "5") (pinfunction "K_5") (pintype "passive"))
    )
    (net (code "40") (name "LED_GREEN") (class "Default")
      (node (ref "MEGA2560PRO1") (pin "A7") (pinfunction "A7_A7") (pintype "bidirectional"))
      (node (ref "R42") (pin "1") (pinfunction "1_1") (pintype "passive"))
    )
    (net (code "41") (name "LED_GREEN2") (class "Default")
      (node (ref "MEGA2560PRO1") (pin "A3") (pinfunction "A3_A3") (pintype "bidirectional"))
      (node (ref "R142") (pin "1") (pinfunction "1_1") (pintype "passive"))
    )
    (net (code "42") (name "LED_GREEN_EXT") (class "Default")
      (node (ref "D10") (pin "C") (pinfunction "C_C") (pintype "passive"))
      (node (ref "R142") (pin "2") (pinfunction "2_2") (pintype "passive"))
      (node (ref "X3") (pin "7") (pinfunction "K_7") (pintype "passive"))
    )
    (net (code "43") (name "LED_RED") (class "Default")
      (node (ref "MEGA2560PRO1") (pin "A5") (pinfunction "A5_A5") (pintype "bidirectional"))
      (node (ref "R40") (pin "1") (pinfunction "1_1") (pintype "passive"))
    )
    (net (code "44") (name "LED_RED2") (class "Default")
      (node (ref "MEGA2560PRO1") (pin "A1") (pinfunction "A1_A1") (pintype "bidirectional"))
      (node (ref "R140") (pin "1") (pinfunction "1_1") (pintype "passive"))
    )
    (net (code "45") (name "LED_RED_EXT") (class "Default")
      (node (ref "D8") (pin "C") (pinfunction "C_C") (pintype "passive"))
      (node (ref "R140") (pin "2") (pinfunction "2_2") (pintype "passive"))
      (node (ref "X3") (pin "5") (pinfunction "K_5") (pintype "passive"))
    )
    (net (code "46") (name "Net-(C29-Pad2)") (class "Default")
      (node (ref "C29") (pin "2") (pinfunction "2_2") (pintype "passive"))
      (node (ref "R41") (pin "2") (pinfunction "2_2") (pintype "passive"))
    )
    (net (code "47") (name "Net-(C31-+)") (class "Default")
      (node (ref "C31") (pin "1") (pinfunction "+_1") (pintype "passive"))
      (node (ref "D14") (pin "1") (pinfunction "K_1") (pintype "bidirectional"))
      (node (ref "U3") (pin "5") (pinfunction "ON/~{OFF}_5") (pintype "bidirectional"))
      (node (ref "U3") (pin "7") (pinfunction "VIN_7") (pintype "bidirectional"))
    )
    (net (code "48") (name "Net-(D5-PadC)") (class "Default")
      (node (ref "D5") (pin "C") (pinfunction "C_C") (pintype "passive"))
      (node (ref "MEGA2560PRO1") (pin "RX") (pinfunction "RX_RX") (pintype "bidirectional"))
    )
    (net (code "49") (name "Net-(D7-PadC)") (class "Default")
      (node (ref "D7") (pin "C") (pinfunction "C_C") (pintype "passive"))
      (node (ref "MEGA2560PRO1") (pin "TX") (pinfunction "TX_TX") (pintype "bidirectional"))
    )
    (net (code "50") (name "Net-(D11-C1A2)") (class "Default")
      (node (ref "C12") (pin "1") (pinfunction "1_1") (pintype "passive"))
      (node (ref "D11") (pin "3") (pinfunction "C1A2_3") (pintype "passive"))
      (node (ref "R23") (pin "2") (pinfunction "2_2") (pintype "passive"))
      (node (ref "R27") (pin "2") (pinfunction "2_2") (pintype "passive"))
      (node (ref "R4") (pin "2") (pinfunction "2_2") (pintype "passive"))
    )
    (net (code "51") (name "Net-(D17-K)") (class "Default")
      (node (ref "C18") (pin "1") (pinfunction "1_1") (pintype "passive"))
      (node (ref "D17") (pin "1") (pinfunction "K_1") (pintype "bidirectional"))
      (node (ref "U4") (pin "2") (pinfunction "HB_2") (pintype "bidirectional"))
    )
    (net (code "52") (name "Net-(D20-K)") (class "Default")
      (node (ref "C27") (pin "2") (pinfunction "2_2") (pintype "passive"))
      (node (ref "C29") (pin "1") (pinfunction "1_1") (pintype "passive"))
      (node (ref "D20") (pin "1") (pinfunction "K_1") (pintype "bidirectional"))
      (node (ref "L1") (pin "1") (pinfunction "P$1_1") (pintype "bidirectional"))
      (node (ref "L1") (pin "4") (pinfunction "P$1_4") (pintype "bidirectional"))
      (node (ref "U3") (pin "8") (pinfunction "LX_8") (pintype "bidirectional"))
    )
    (net (code "53") (name "Net-(D111-C1A2)") (class "Default")
      (node (ref "C112") (pin "1") (pinfunction "1_1") (pintype "passive"))
      (node (ref "D111") (pin "3") (pinfunction "C1A2_3") (pintype "passive"))
      (node (ref "R104") (pin "2") (pinfunction "2_2") (pintype "passive"))
      (node (ref "R123") (pin "2") (pinfunction "2_2") (pintype "passive"))
      (node (ref "R127") (pin "2") (pinfunction "2_2") (pintype "passive"))
    )
    (net (code "54") (name "Net-(D211-C1A2)") (class "Default")
      (node (ref "C212") (pin "1") (pinfunction "1_1") (pintype "passive"))
      (node (ref "D211") (pin "3") (pinfunction "C1A2_3") (pintype "passive"))
      (node (ref "R204") (pin "2") (pinfunction "2_2") (pintype "passive"))
      (node (ref "R223") (pin "2") (pinfunction "2_2") (pintype "passive"))
      (node (ref "R227") (pin "2") (pinfunction "2_2") (pintype "passive"))
    )
    (net (code "55") (name "Net-(GREEN-A)") (class "Default")
      (node (ref "GREEN") (pin "2") (pinfunction "A_2") (pintype "bidirectional"))
      (node (ref "LED1") (pin "3") (pinfunction "ANODE_GREEN_3") (pintype "bidirectional"))
      (node (ref "R42") (pin "2") (pinfunction "2_2") (pintype "passive"))
    )
    (net (code "56") (name "Net-(LED1-ANODE_RED)") (class "Default")
      (node (ref "LED1") (pin "1") (pinfunction "ANODE_RED_1") (pintype "bidirectional"))
      (node (ref "R40") (pin "2") (pinfunction "2_2") (pintype "passive"))
      (node (ref "RED") (pin "2") (pinfunction "A_2") (pintype "bidirectional"))
    )
    (net (code "57") (name "Net-(Q1-B)") (class "Default")
      (node (ref "Q1") (pin "1") (pinfunction "B_1") (pintype "passive"))
      (node (ref "R8") (pin "1") (pinfunction "1_1") (pintype "passive"))
    )
    (net (code "58") (name "Net-(Q2-G)") (class "Default")
      (node (ref "Q2") (pin "4") (pinfunction "G_4") (pintype "bidirectional"))
      (node (ref "R29") (pin "2") (pinfunction "2_2") (pintype "passive"))
    )
    (net (code "59") (name "Net-(Q3-G)") (class "Default")
      (node (ref "Q3") (pin "4") (pinfunction "G_4") (pintype "bidirectional"))
      (node (ref "R26") (pin "2") (pinfunction "2_2") (pintype "passive"))
    )
    (net (code "60") (name "Net-(Q101-B)") (class "Default")
      (node (ref "Q101") (pin "1") (pinfunction "B_1") (pintype "passive"))
      (node (ref "R108") (pin "1") (pinfunction "1_1") (pintype "passive"))
    )
    (net (code "61") (name "Net-(Q201-B)") (class "Default")
      (node (ref "Q201") (pin "1") (pinfunction "B_1") (pintype "passive"))
      (node (ref "R208") (pin "1") (pinfunction "1_1") (pintype "passive"))
    )
    (net (code "62") (name "Net-(U1-VBUS)") (class "Default")
      (node (ref "C4") (pin "1") (pinfunction "1_1") (pintype "passive"))
      (node (ref "D4") (pin "C") (pinfunction "C_C") (pintype "passive"))
      (node (ref "R1") (pin "1") (pinfunction "1_1") (pintype "passive"))
      (node (ref "U1") (pin "8") (pinfunction "VBUS_8") (pintype "input"))
    )
    (net (code "63") (name "Net-(U1-VIN+)") (class "Default")
      (node (ref "C2") (pin "1") (pinfunction "1_1") (pintype "passive"))
      (node (ref "R2") (pin "1") (pinfunction "1_1") (pintype "passive"))
      (node (ref "U1") (pin "10") (pinfunction "VIN+_10") (pintype "power_in"))
    )
    (net (code "64") (name "Net-(U1-VIN-)") (class "Default")
      (node (ref "C2") (pin "2") (pinfunction "2_2") (pintype "passive"))
      (node (ref "R9") (pin "1") (pinfunction "1_1") (pintype "passive"))
      (node (ref "U1") (pin "9") (pinfunction "VIN-_9") (pintype "power_in"))
    )
    (net (code "65") (name "Net-(U2-VBUS)") (class "Default")
      (node (ref "C104") (pin "1") (pinfunction "1_1") (pintype "passive"))
      (node (ref "D104") (pin "C") (pinfunction "C_C") (pintype "passive"))
      (node (ref "R101") (pin "1") (pinfunction "1_1") (pintype "passive"))
      (node (ref "U2") (pin "8") (pinfunction "VBUS_8") (pintype "input"))
    )
    (net (code "66") (name "Net-(U2-VIN+)") (class "Default")
      (node (ref "C102") (pin "1") (pinfunction "1_1") (pintype "passive"))
      (node (ref "R102") (pin "1") (pinfunction "1_1") (pintype "passive"))
      (node (ref "U2") (pin "10") (pinfunction "VIN+_10") (pintype "power_in"))
    )
    (net (code "67") (name "Net-(U2-VIN-)") (class "Default")
      (node (ref "C102") (pin "2") (pinfunction "2_2") (pintype "passive"))
      (node (ref "R109") (pin "1") (pinfunction "1_1") (pintype "passive"))
      (node (ref "U2") (pin "9") (pinfunction "VIN-_9") (pintype "power_in"))
    )
    (net (code "68") (name "Net-(U3-BST)") (class "Default")
      (node (ref "C27") (pin "1") (pinfunction "1_1") (pintype "passive"))
      (node (ref "U3") (pin "1") (pinfunction "BST_1") (pintype "bidirectional"))
    )
    (net (code "69") (name "Net-(U3-FB)") (class "Default")
      (node (ref "R39") (pin "2") (pinfunction "2_2") (pintype "passive"))
      (node (ref "R43") (pin "1") (pinfunction "1_1") (pintype "passive"))
      (node (ref "U3") (pin "4") (pinfunction "FB_4") (pintype "bidirectional"))
    )
    (net (code "70") (name "Net-(U3-VD)") (class "Default")
      (node (ref "C25") (pin "1") (pinfunction "1_1") (pintype "passive"))
      (node (ref "U3") (pin "2") (pinfunction "VD_2") (pintype "bidirectional"))
    )
    (net (code "71") (name "Net-(U4-HO)") (class "Default")
      (node (ref "R26") (pin "1") (pinfunction "1_1") (pintype "passive"))
      (node (ref "R29") (pin "1") (pinfunction "1_1") (pintype "passive"))
      (node (ref "U4") (pin "3") (pinfunction "HO_3") (pintype "bidirectional"))
    )
    (net (code "72") (name "Net-(U4-LO)") (class "Default")
      (node (ref "R19") (pin "1") (pinfunction "1_1") (pintype "passive"))
      (node (ref "U4") (pin "8") (pinfunction "LO_8") (pintype "bidirectional"))
    )
    (net (code "73") (name "Net-(U5-IN1)") (class "Default")
      (node (ref "C11") (pin "1") (pinfunction "1_1") (pintype "passive"))
      (node (ref "R7") (pin "1") (pinfunction "1_1") (pintype "passive"))
      (node (ref "U5") (pin "2") (pinfunction "IN1_2") (pintype "bidirectional"))
    )
    (net (code "74") (name "Net-(U5-RADJ)") (class "Default")
      (node (ref "R31") (pin "1") (pinfunction "1_1") (pintype "passive"))
      (node (ref "U5") (pin "1") (pinfunction "RADJ_1") (pintype "bidirectional"))
    )
    (net (code "75") (name "RX-1") (class "Default")
      (node (ref "D106") (pin "C") (pinfunction "C_C") (pintype "passive"))
      (node (ref "MEGA2560PRO1") (pin "D19") (pinfunction "D19_D19") (pintype "bidirectional"))
      (node (ref "X4") (pin "4") (pinfunction "K_4") (pintype "passive"))
    )
    (net (code "76") (name "RX-2") (class "Default")
      (node (ref "D6") (pin "C") (pinfunction "C_C") (pintype "passive"))
      (node (ref "MEGA2560PRO1") (pin "D17") (pinfunction "D17_D17") (pintype "bidirectional"))
      (node (ref "X4") (pin "1") (pinfunction "K_1") (pintype "passive"))
    )
    (net (code "77") (name "SCL") (class "Default")
      (node (ref "I2C-2") (pin "3") (pinfunction "3_3") (pintype "bidirectional"))
      (node (ref "IC2-1") (pin "3") (pinfunction "3_3") (pintype "bidirectional"))
      (node (ref "MEGA2560PRO1") (pin "D21") (pinfunction "D21_D21") (pintype "bidirectional"))
      (node (ref "R35") (pin "1") (pinfunction "1_1") (pintype "passive"))
      (node (ref "U1") (pin "5") (pinfunction "SCL_5") (pintype "input"))
      (node (ref "U2") (pin "5") (pinfunction "SCL_5") (pintype "input"))
    )
    (net (code "78") (name "SDA") (class "Default")
      (node (ref "I2C-2") (pin "4") (pinfunction "4_4") (pintype "bidirectional"))
      (node (ref "IC2-1") (pin "4") (pinfunction "4_4") (pintype "bidirectional"))
      (node (ref "MEGA2560PRO1") (pin "D20") (pinfunction "D20_D20") (pintype "bidirectional"))
      (node (ref "R37") (pin "1") (pinfunction "1_1") (pintype "passive"))
      (node (ref "U1") (pin "4") (pinfunction "SDA_4") (pintype "bidirectional"))
      (node (ref "U2") (pin "4") (pinfunction "SDA_4") (pintype "bidirectional"))
    )
    (net (code "79") (name "STATOR") (class "Default")
      (node (ref "R7") (pin "2") (pinfunction "2_2") (pintype "passive"))
      (node (ref "X1") (pin "5") (pinfunction "KL_5") (pintype "passive"))
    )
    (net (code "80") (name "STATOR_IRQ") (class "Default")
      (node (ref "MEGA2560PRO1") (pin "D2") (pinfunction "D2_D2") (pintype "bidirectional"))
      (node (ref "U4") (pin "6") (pinfunction "LI_6") (pintype "bidirectional"))
      (node (ref "U5") (pin "7") (pinfunction "OUT1_7") (pintype "bidirectional"))
    )
    (net (code "81") (name "TACH_OUT") (class "Default")
      (node (ref "R19") (pin "2") (pinfunction "2_2") (pintype "passive"))
      (node (ref "X1") (pin "6") (pinfunction "KL_6") (pintype "passive"))
    )
    (net (code "82") (name "TX-1") (class "Default")
      (node (ref "D109") (pin "C") (pinfunction "C_C") (pintype "passive"))
      (node (ref "MEGA2560PRO1") (pin "D18") (pinfunction "D18_D18") (pintype "bidirectional"))
      (node (ref "X4") (pin "6") (pinfunction "K_6") (pintype "passive"))
    )
    (net (code "83") (name "TX-2") (class "Default")
      (node (ref "D9") (pin "C") (pinfunction "C_C") (pintype "passive"))
      (node (ref "MEGA2560PRO1") (pin "D16") (pinfunction "D16_D16") (pintype "bidirectional"))
      (node (ref "X4") (pin "3") (pinfunction "K_3") (pintype "passive"))
    )
    (net (code "84") (name "VDD") (class "Default")
      (node (ref "C30") (pin "1") (pinfunction "1_1") (pintype "passive"))
      (node (ref "C32") (pin "1") (pinfunction "+_1") (pintype "passive"))
      (node (ref "D17") (pin "2") (pinfunction "A_2") (pintype "bidirectional"))
      (node (ref "L1") (pin "2") (pinfunction "P$2_2") (pintype "bidirectional"))
      (node (ref "L1") (pin "3") (pinfunction "P$2_3") (pintype "bidirectional"))
      (node (ref "MEGA2560PRO1") (pin "VIN@1") (pinfunction "VIN_VIN@1") (pintype "bidirectional"))
      (node (ref "MEGA2560PRO1") (pin "VIN@2") (pinfunction "VIN_VIN@2") (pintype "bidirectional"))
      (node (ref "R43") (pin "2") (pinfunction "2_2") (pintype "passive"))
      (node (ref "TP-VDD") (pin "TP") (pinfunction "TP_TP") (pintype "input"))
      (node (ref "U4") (pin "1") (pinfunction "VDD_1") (pintype "bidirectional"))
    )
    (net (code "85") (name "unconnected-(FIDUCIAL1-PadP$1)") (class "Default")
      (node (ref "FIDUCIAL1") (pin "P$1") (pinfunction "P$1_P$1") (pintype "bidirectional"))
    )
    (net (code "86") (name "unconnected-(FIDUCIAL2-PadP$1)") (class "Default")
      (node (ref "FIDUCIAL2") (pin "P$1") (pinfunction "P$1_P$1") (pintype "bidirectional"))
    )
    (net (code "87") (name "unconnected-(MEGA2560PRO1-3V3-Pad3V3@1)") (class "Default")
      (node (ref "MEGA2560PRO1") (pin "3V3@1") (pinfunction "3V3_3V3@1") (pintype "bidirectional"))
    )
    (net (code "88") (name "unconnected-(MEGA2560PRO1-3V3-Pad3V3@2)") (class "Default")
      (node (ref "MEGA2560PRO1") (pin "3V3@2") (pinfunction "3V3_3V3@2") (pintype "bidirectional"))
    )
    (net (code "89") (name "unconnected-(MEGA2560PRO1-PadA4)") (class "Default")
      (node (ref "MEGA2560PRO1") (pin "A4") (pinfunction "A4_A4") (pintype "bidirectional"))
    )
    (net (code "90") (name "unconnected-(MEGA2560PRO1-PadA6)") (class "Default")
      (node (ref "MEGA2560PRO1") (pin "A6") (pinfunction "A6_A6") (pintype "bidirectional"))
    )
    (net (code "91") (name "unconnected-(MEGA2560PRO1-PadA9)") (class "Default")
      (node (ref "MEGA2560PRO1") (pin "A9") (pinfunction "A9_A9") (pintype "bidirectional"))
    )
    (net (code "92") (name "unconnected-(MEGA2560PRO1-PadA10)") (class "Default")
      (node (ref "MEGA2560PRO1") (pin "A10") (pinfunction "A10_A10") (pintype "bidirectional"))
    )
    (net (code "93") (name "unconnected-(MEGA2560PRO1-PadA11)") (class "Default")
      (node (ref "MEGA2560PRO1") (pin "A11") (pinfunction "A11_A11") (pintype "bidirectional"))
    )
    (net (code "94") (name "unconnected-(MEGA2560PRO1-PadA12)") (class "Default")
      (node (ref "MEGA2560PRO1") (pin "A12") (pinfunction "A12_A12") (pintype "bidirectional"))
    )
    (net (code "95") (name "unconnected-(MEGA2560PRO1-PadA13)") (class "Default")
      (node (ref "MEGA2560PRO1") (pin "A13") (pinfunction "A13_A13") (pintype "bidirectional"))
    )
    (net (code "96") (name "unconnected-(MEGA2560PRO1-PadA14)") (class "Default")
      (node (ref "MEGA2560PRO1") (pin "A14") (pinfunction "A14_A14") (pintype "bidirectional"))
    )
    (net (code "97") (name "unconnected-(MEGA2560PRO1-PadA15)") (class "Default")
      (node (ref "MEGA2560PRO1") (pin "A15") (pinfunction "A15_A15") (pintype "bidirectional"))
    )
    (net (code "98") (name "unconnected-(MEGA2560PRO1-PadAREF)") (class "Default")
      (node (ref "MEGA2560PRO1") (pin "AREF") (pinfunction "AREF_AREF") (pintype "bidirectional"))
    )
    (net (code "99") (name "unconnected-(MEGA2560PRO1-PadD15)") (class "Default")
      (node (ref "MEGA2560PRO1") (pin "D15") (pinfunction "D15_D15") (pintype "bidirectional"))
    )
    (net (code "100") (name "unconnected-(MEGA2560PRO1-PadD22)") (class "Default")
      (node (ref "MEGA2560PRO1") (pin "D22") (pinfunction "D22_D22") (pintype "bidirectional"))
    )
    (net (code "101") (name "unconnected-(MEGA2560PRO1-PadD23)") (class "Default")
      (node (ref "MEGA2560PRO1") (pin "D23") (pinfunction "D23_D23") (pintype "bidirectional"))
    )
    (net (code "102") (name "unconnected-(MEGA2560PRO1-PadD24)") (class "Default")
      (node (ref "MEGA2560PRO1") (pin "D24") (pinfunction "D24_D24") (pintype "bidirectional"))
    )
    (net (code "103") (name "unconnected-(MEGA2560PRO1-PadD25)") (class "Default")
      (node (ref "MEGA2560PRO1") (pin "D25") (pinfunction "D25_D25") (pintype "bidirectional"))
    )
    (net (code "104") (name "unconnected-(MEGA2560PRO1-PadD26)") (class "Default")
      (node (ref "MEGA2560PRO1") (pin "D26") (pinfunction "D26_D26") (pintype "bidirectional"))
    )
    (net (code "105") (name "unconnected-(MEGA2560PRO1-PadD28)") (class "Default")
      (node (ref "MEGA2560PRO1") (pin "D28") (pinfunction "D28_D28") (pintype "bidirectional"))
    )
    (net (code "106") (name "unconnected-(MEGA2560PRO1-PadD30)") (class "Default")
      (node (ref "MEGA2560PRO1") (pin "D30") (pinfunction "D30_D30") (pintype "bidirectional"))
    )
    (net (code "107") (name "unconnected-(MEGA2560PRO1-PadD32)") (class "Default")
      (node (ref "MEGA2560PRO1") (pin "D32") (pinfunction "D32_D32") (pintype "bidirectional"))
    )
    (net (code "108") (name "unconnected-(MEGA2560PRO1-PadD33)") (class "Default")
      (node (ref "MEGA2560PRO1") (pin "D33") (pinfunction "D33_D33") (pintype "bidirectional"))
    )
    (net (code "109") (name "unconnected-(MEGA2560PRO1-PadD34)") (class "Default")
      (node (ref "MEGA2560PRO1") (pin "D34") (pinfunction "D34_D34") (pintype "bidirectional"))
    )
    (net (code "110") (name "unconnected-(MEGA2560PRO1-PadD35)") (class "Default")
      (node (ref "MEGA2560PRO1") (pin "D35") (pinfunction "D35_D35") (pintype "bidirectional"))
    )
    (net (code "111") (name "unconnected-(MEGA2560PRO1-PadD36)") (class "Default")
      (node (ref "MEGA2560PRO1") (pin "D36") (pinfunction "D36_D36") (pintype "bidirectional"))
    )
    (net (code "112") (name "unconnected-(MEGA2560PRO1-PadD37)") (class "Default")
      (node (ref "MEGA2560PRO1") (pin "D37") (pinfunction "D37_D37") (pintype "bidirectional"))
    )
    (net (code "113") (name "unconnected-(MEGA2560PRO1-PadD38)") (class "Default")
      (node (ref "MEGA2560PRO1") (pin "D38") (pinfunction "D38_D38") (pintype "bidirectional"))
    )
    (net (code "114") (name "unconnected-(MEGA2560PRO1-PadD39)") (class "Default")
      (node (ref "MEGA2560PRO1") (pin "D39") (pinfunction "D39_D39") (pintype "bidirectional"))
    )
    (net (code "115") (name "unconnected-(MEGA2560PRO1-PadD40)") (class "Default")
      (node (ref "MEGA2560PRO1") (pin "D40") (pinfunction "D40_D40") (pintype "bidirectional"))
    )
    (net (code "116") (name "unconnected-(MEGA2560PRO1-PadD41)") (class "Default")
      (node (ref "MEGA2560PRO1") (pin "D41") (pinfunction "D41_D41") (pintype "bidirectional"))
    )
    (net (code "117") (name "unconnected-(MEGA2560PRO1-PadD42)") (class "Default")
      (node (ref "MEGA2560PRO1") (pin "D42") (pinfunction "D42_D42") (pintype "bidirectional"))
    )
    (net (code "118") (name "unconnected-(MEGA2560PRO1-PadD43)") (class "Default")
      (node (ref "MEGA2560PRO1") (pin "D43") (pinfunction "D43_D43") (pintype "bidirectional"))
    )
    (net (code "119") (name "unconnected-(MEGA2560PRO1-PadD44)") (class "Default")
      (node (ref "MEGA2560PRO1") (pin "D44") (pinfunction "D44_D44") (pintype "bidirectional"))
    )
    (net (code "120") (name "unconnected-(MEGA2560PRO1-PadD45)") (class "Default")
      (node (ref "MEGA2560PRO1") (pin "D45") (pinfunction "D45_D45") (pintype "bidirectional"))
    )
    (net (code "121") (name "unconnected-(MEGA2560PRO1-PadD46)") (class "Default")
      (node (ref "MEGA2560PRO1") (pin "D46") (pinfunction "D46_D46") (pintype "bidirectional"))
    )
    (net (code "122") (name "unconnected-(MEGA2560PRO1-PadD47)") (class "Default")
      (node (ref "MEGA2560PRO1") (pin "D47") (pinfunction "D47_D47") (pintype "bidirectional"))
    )
    (net (code "123") (name "unconnected-(MEGA2560PRO1-PadD48)") (class "Default")
      (node (ref "MEGA2560PRO1") (pin "D48") (pinfunction "D48_D48") (pintype "bidirectional"))
    )
    (net (code "124") (name "unconnected-(MEGA2560PRO1-PadD49)") (class "Default")
      (node (ref "MEGA2560PRO1") (pin "D49") (pinfunction "D49_D49") (pintype "bidirectional"))
    )
    (net (code "125") (name "unconnected-(MEGA2560PRO1-PadD50)") (class "Default")
      (node (ref "MEGA2560PRO1") (pin "D50") (pinfunction "D50_D50") (pintype "bidirectional"))
    )
    (net (code "126") (name "unconnected-(MEGA2560PRO1-PadD51)") (class "Default")
      (node (ref "MEGA2560PRO1") (pin "D51") (pinfunction "D51_D51") (pintype "bidirectional"))
    )
    (net (code "127") (name "unconnected-(MEGA2560PRO1-PadD52)") (class "Default")
      (node (ref "MEGA2560PRO1") (pin "D52") (pinfunction "D52_D52") (pintype "bidirectional"))
    )
    (net (code "128") (name "unconnected-(MEGA2560PRO1-PadD53)") (class "Default")
      (node (ref "MEGA2560PRO1") (pin "D53") (pinfunction "D53_D53") (pintype "bidirectional"))
    )
    (net (code "129") (name "unconnected-(MEGA2560PRO1-PadMISO)") (class "Default")
      (node (ref "MEGA2560PRO1") (pin "MISO") (pinfunction "MISO_MISO") (pintype "bidirectional"))
    )
    (net (code "130") (name "unconnected-(MEGA2560PRO1-PadMOSI)") (class "Default")
      (node (ref "MEGA2560PRO1") (pin "MOSI") (pinfunction "MOSI_MOSI") (pintype "bidirectional"))
    )
    (net (code "131") (name "unconnected-(MEGA2560PRO1-PadRESET)") (class "Default")
      (node (ref "MEGA2560PRO1") (pin "RESET") (pinfunction "RESET_RESET") (pintype "bidirectional"))
    )
    (net (code "132") (name "unconnected-(MEGA2560PRO1-PadRST)") (class "Default")
      (node (ref "MEGA2560PRO1") (pin "RST") (pinfunction "RST_RST") (pintype "bidirectional"))
    )
    (net (code "133") (name "unconnected-(MEGA2560PRO1-PadSCK)") (class "Default")
      (node (ref "MEGA2560PRO1") (pin "SCK") (pinfunction "SCK_SCK") (pintype "bidirectional"))
    )
    (net (code "134") (name "unconnected-(U1-ALERT-Pad3)") (class "Default")
      (node (ref "U1") (pin "3") (pinfunction "ALERT_3") (pintype "output"))
    )
    (net (code "135") (name "unconnected-(U2-ALERT-Pad3)") (class "Default")
      (node (ref "U2") (pin "3") (pinfunction "ALERT_3") (pintype "output"))
    )
    (net (code "136") (name "unconnected-(U5-IN2-Pad3)") (class "Default")
      (node (ref "U5") (pin "3") (pinfunction "IN2_3") (pintype "no_connect"))
    )
    (net (code "137") (name "unconnected-(U5-OUT2-Pad6)") (class "Default")
      (node (ref "U5") (pin "6") (pinfunction "OUT2_6") (pintype "no_connect"))
    )
  )
)
